# 26_PP0_SSMII.net
KiCad netlist of a schematic drawn in Altium Designer
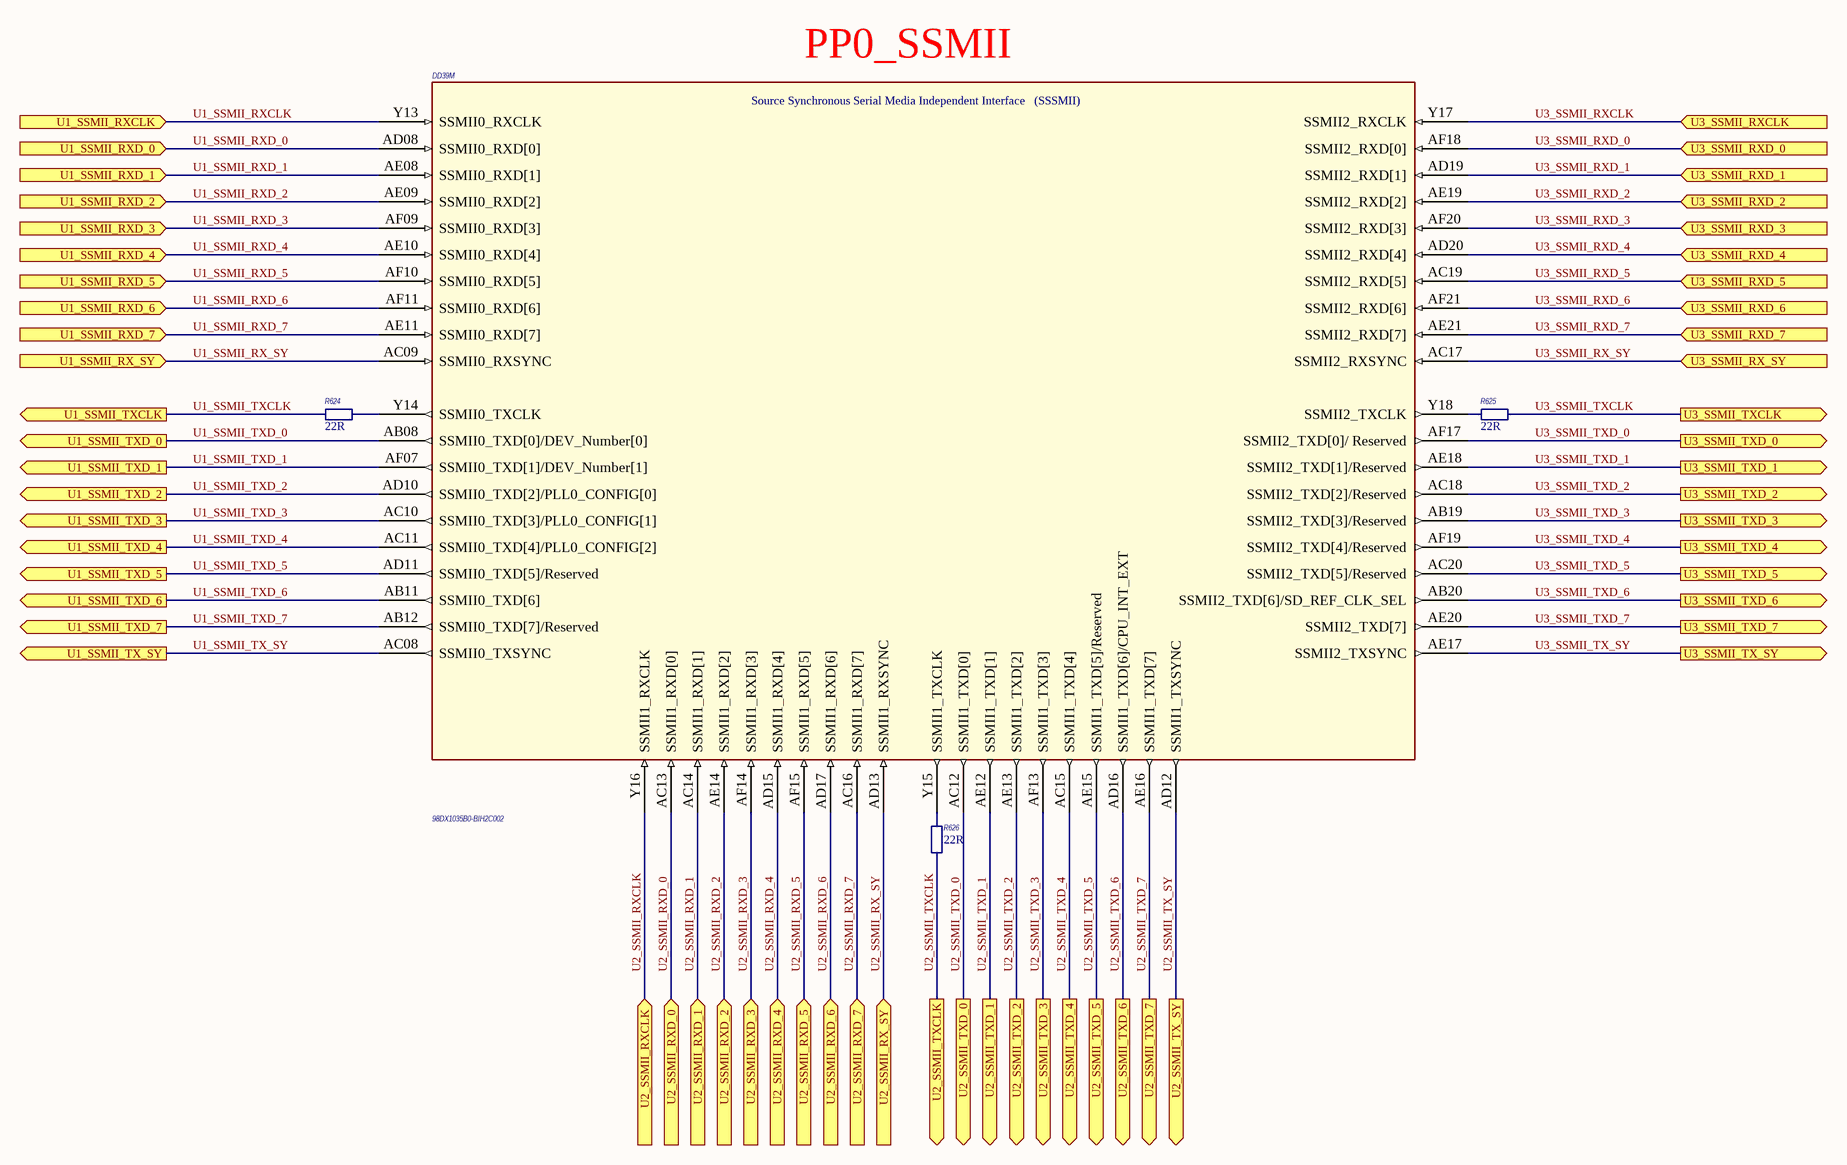
[diagram p0: 26_PP0_SSMII.SchDoc]

(export (version "E")
  (design (tool "Eeschema 10.0.6"))
  (components
    (comp (ref "DD39")
      (value "98DX1035B0-BIH2C002")
      (footprint "HSBGA617_27X27_1MM")
      (description "IC 24-PORT FE  4-PORT 2.5GE L2 ENTRY-LEVEL, CPU")
      (fields
        (field (name "CUSTOMER PART NUMBER") "Микросхема, 98DX1035B0-BIH2C002, IC 24-PORT FE 4-PORT 2.5GE L2 ENTRY-LEVEL, HSBGA617SBGA617")
        (field (name "MANUFACTURER") "Marvell Technology Group")
      )
      (libsource (lib "DIGITAL and ANALIG ICs") (part "98DX1035A1-BIH2C002"))
    )
    (comp (ref "R624")
      (value "ERJ-2RKF22R0X")
      (footprint "R0402_IPC High Density")
      (description "R0402, 22R 1%")
      (fields
        (field (name "MANUFACTURER") "Panasonic")
        (field (name "RESISTANCE") "22R")
        (field (name "CUSTOMER PART NUMBER") "Резистор, 22R, 0402, 1%")
      )
      (libsource (lib "RESISTOR") (part "ERJ-2RKF22R0X"))
    )
    (comp (ref "R625")
      (value "ERJ-2RKF22R0X")
      (footprint "R0402_IPC High Density")
      (description "R0402, 22R 1%")
      (fields
        (field (name "MANUFACTURER") "Panasonic")
        (field (name "RESISTANCE") "22R")
        (field (name "CUSTOMER PART NUMBER") "Резистор, 22R, 0402, 1%")
      )
      (libsource (lib "RESISTOR") (part "ERJ-2RKF22R0X"))
    )
    (comp (ref "R626")
      (value "ERJ-2RKF22R0X")
      (footprint "R0402_IPC High Density")
      (description "R0402, 22R 1%")
      (fields
        (field (name "MANUFACTURER") "Panasonic")
        (field (name "RESISTANCE") "22R")
        (field (name "CUSTOMER PART NUMBER") "Резистор, 22R, 0402, 1%")
      )
      (libsource (lib "RESISTOR") (part "ERJ-2RKF22R0X"))
    )
  )
  (nets
    (net (code "1") (name "/U1_SSMII_RXCLK") (class "Default")
      (node (ref "DD39") (pin "Y13") (pinfunction "SSMII0_RXCLK_Y13") (pintype "input"))
    )
    (net (code "2") (name "/U1_SSMII_RXD_0") (class "Default")
      (node (ref "DD39") (pin "AD08") (pinfunction "SSMII0_RXD[0]_AD08") (pintype "input"))
    )
    (net (code "3") (name "/U1_SSMII_RXD_1") (class "Default")
      (node (ref "DD39") (pin "AE08") (pinfunction "SSMII0_RXD[1]_AE08") (pintype "input"))
    )
    (net (code "4") (name "/U1_SSMII_RXD_2") (class "Default")
      (node (ref "DD39") (pin "AE09") (pinfunction "SSMII0_RXD[2]_AE09") (pintype "input"))
    )
    (net (code "5") (name "/U1_SSMII_RXD_3") (class "Default")
      (node (ref "DD39") (pin "AF09") (pinfunction "SSMII0_RXD[3]_AF09") (pintype "input"))
    )
    (net (code "6") (name "/U1_SSMII_RXD_4") (class "Default")
      (node (ref "DD39") (pin "AE10") (pinfunction "SSMII0_RXD[4]_AE10") (pintype "input"))
    )
    (net (code "7") (name "/U1_SSMII_RXD_5") (class "Default")
      (node (ref "DD39") (pin "AF10") (pinfunction "SSMII0_RXD[5]_AF10") (pintype "input"))
    )
    (net (code "8") (name "/U1_SSMII_RXD_6") (class "Default")
      (node (ref "DD39") (pin "AF11") (pinfunction "SSMII0_RXD[6]_AF11") (pintype "input"))
    )
    (net (code "9") (name "/U1_SSMII_RXD_7") (class "Default")
      (node (ref "DD39") (pin "AE11") (pinfunction "SSMII0_RXD[7]_AE11") (pintype "input"))
    )
    (net (code "10") (name "/U1_SSMII_RX_SY") (class "Default")
      (node (ref "DD39") (pin "AC09") (pinfunction "SSMII0_RXSYNC_AC09") (pintype "input"))
    )
    (net (code "11") (name "/U1_SSMII_TXCLK") (class "Default")
      (node (ref "R624") (pin "2") (pintype "passive"))
    )
    (net (code "12") (name "/U1_SSMII_TXD_0") (class "Default")
      (node (ref "DD39") (pin "AB08") (pinfunction "SSMII0_TXD[0]/DEV_Number[0]_AB08") (pintype "output"))
    )
    (net (code "13") (name "/U1_SSMII_TXD_1") (class "Default")
      (node (ref "DD39") (pin "AF07") (pinfunction "SSMII0_TXD[1]/DEV_Number[1]_AF07") (pintype "output"))
    )
    (net (code "14") (name "/U1_SSMII_TXD_2") (class "Default")
      (node (ref "DD39") (pin "AD10") (pinfunction "SSMII0_TXD[2]/PLL0_CONFIG[0]_AD10") (pintype "output"))
    )
    (net (code "15") (name "/U1_SSMII_TXD_3") (class "Default")
      (node (ref "DD39") (pin "AC10") (pinfunction "SSMII0_TXD[3]/PLL0_CONFIG[1]_AC10") (pintype "output"))
    )
    (net (code "16") (name "/U1_SSMII_TXD_4") (class "Default")
      (node (ref "DD39") (pin "AC11") (pinfunction "SSMII0_TXD[4]/PLL0_CONFIG[2]_AC11") (pintype "output"))
    )
    (net (code "17") (name "/U1_SSMII_TXD_5") (class "Default")
      (node (ref "DD39") (pin "AD11") (pinfunction "SSMII0_TXD[5]/Reserved_AD11") (pintype "output"))
    )
    (net (code "18") (name "/U1_SSMII_TXD_6") (class "Default")
      (node (ref "DD39") (pin "AB11") (pinfunction "SSMII0_TXD[6]_AB11") (pintype "output"))
    )
    (net (code "19") (name "/U1_SSMII_TXD_7") (class "Default")
      (node (ref "DD39") (pin "AB12") (pinfunction "SSMII0_TXD[7]/Reserved_AB12") (pintype "output"))
    )
    (net (code "20") (name "/U1_SSMII_TX_SY") (class "Default")
      (node (ref "DD39") (pin "AC08") (pinfunction "SSMII0_TXSYNC_AC08") (pintype "output"))
    )
    (net (code "21") (name "/U2_SSMII_RXCLK") (class "Default")
      (node (ref "DD39") (pin "Y16") (pinfunction "SSMII1_RXCLK_Y16") (pintype "input"))
    )
    (net (code "22") (name "/U2_SSMII_RXD_0") (class "Default")
      (node (ref "DD39") (pin "AC13") (pinfunction "SSMII1_RXD[0]_AC13") (pintype "input"))
    )
    (net (code "23") (name "/U2_SSMII_RXD_1") (class "Default")
      (node (ref "DD39") (pin "AC14") (pinfunction "SSMII1_RXD[1]_AC14") (pintype "input"))
    )
    (net (code "24") (name "/U2_SSMII_RXD_2") (class "Default")
      (node (ref "DD39") (pin "AE14") (pinfunction "SSMII1_RXD[2]_AE14") (pintype "input"))
    )
    (net (code "25") (name "/U2_SSMII_RXD_3") (class "Default")
      (node (ref "DD39") (pin "AF14") (pinfunction "SSMII1_RXD[3]_AF14") (pintype "input"))
    )
    (net (code "26") (name "/U2_SSMII_RXD_4") (class "Default")
      (node (ref "DD39") (pin "AD15") (pinfunction "SSMII1_RXD[4]_AD15") (pintype "input"))
    )
    (net (code "27") (name "/U2_SSMII_RXD_5") (class "Default")
      (node (ref "DD39") (pin "AF15") (pinfunction "SSMII1_RXD[5]_AF15") (pintype "input"))
    )
    (net (code "28") (name "/U2_SSMII_RXD_6") (class "Default")
      (node (ref "DD39") (pin "AD17") (pinfunction "SSMII1_RXD[6]_AD17") (pintype "input"))
    )
    (net (code "29") (name "/U2_SSMII_RXD_7") (class "Default")
      (node (ref "DD39") (pin "AC16") (pinfunction "SSMII1_RXD[7]_AC16") (pintype "input"))
    )
    (net (code "30") (name "/U2_SSMII_RX_SY") (class "Default")
      (node (ref "DD39") (pin "AD13") (pinfunction "SSMII1_RXSYNC_AD13") (pintype "input"))
    )
    (net (code "31") (name "/U2_SSMII_TXCLK") (class "Default")
      (node (ref "R626") (pin "2") (pintype "passive"))
    )
    (net (code "32") (name "/U2_SSMII_TXD_0") (class "Default")
      (node (ref "DD39") (pin "AC12") (pinfunction "SSMII1_TXD[0]_AC12") (pintype "output"))
    )
    (net (code "33") (name "/U2_SSMII_TXD_1") (class "Default")
      (node (ref "DD39") (pin "AE12") (pinfunction "SSMII1_TXD[1]_AE12") (pintype "output"))
    )
    (net (code "34") (name "/U2_SSMII_TXD_2") (class "Default")
      (node (ref "DD39") (pin "AE13") (pinfunction "SSMII1_TXD[2]_AE13") (pintype "output"))
    )
    (net (code "35") (name "/U2_SSMII_TXD_3") (class "Default")
      (node (ref "DD39") (pin "AF13") (pinfunction "SSMII1_TXD[3]_AF13") (pintype "output"))
    )
    (net (code "36") (name "/U2_SSMII_TXD_4") (class "Default")
      (node (ref "DD39") (pin "AC15") (pinfunction "SSMII1_TXD[4]_AC15") (pintype "output"))
    )
    (net (code "37") (name "/U2_SSMII_TXD_5") (class "Default")
      (node (ref "DD39") (pin "AE15") (pinfunction "SSMII1_TXD[5]/Reserved_AE15") (pintype "output"))
    )
    (net (code "38") (name "/U2_SSMII_TXD_6") (class "Default")
      (node (ref "DD39") (pin "AD16") (pinfunction "SSMII1_TXD[6]/CPU_INT_EXT_AD16") (pintype "output"))
    )
    (net (code "39") (name "/U2_SSMII_TXD_7") (class "Default")
      (node (ref "DD39") (pin "AE16") (pinfunction "SSMII1_TXD[7]_AE16") (pintype "output"))
    )
    (net (code "40") (name "/U2_SSMII_TX_SY") (class "Default")
      (node (ref "DD39") (pin "AD12") (pinfunction "SSMII1_TXSYNC_AD12") (pintype "output"))
    )
    (net (code "41") (name "/U3_SSMII_RXCLK") (class "Default")
      (node (ref "DD39") (pin "Y17") (pinfunction "SSMII2_RXCLK_Y17") (pintype "input"))
    )
    (net (code "42") (name "/U3_SSMII_RXD_0") (class "Default")
      (node (ref "DD39") (pin "AF18") (pinfunction "SSMII2_RXD[0]_AF18") (pintype "input"))
    )
    (net (code "43") (name "/U3_SSMII_RXD_1") (class "Default")
      (node (ref "DD39") (pin "AD19") (pinfunction "SSMII2_RXD[1]_AD19") (pintype "input"))
    )
    (net (code "44") (name "/U3_SSMII_RXD_2") (class "Default")
      (node (ref "DD39") (pin "AE19") (pinfunction "SSMII2_RXD[2]_AE19") (pintype "input"))
    )
    (net (code "45") (name "/U3_SSMII_RXD_3") (class "Default")
      (node (ref "DD39") (pin "AF20") (pinfunction "SSMII2_RXD[3]_AF20") (pintype "input"))
    )
    (net (code "46") (name "/U3_SSMII_RXD_4") (class "Default")
      (node (ref "DD39") (pin "AD20") (pinfunction "SSMII2_RXD[4]_AD20") (pintype "input"))
    )
    (net (code "47") (name "/U3_SSMII_RXD_5") (class "Default")
      (node (ref "DD39") (pin "AC19") (pinfunction "SSMII2_RXD[5]_AC19") (pintype "input"))
    )
    (net (code "48") (name "/U3_SSMII_RXD_6") (class "Default")
      (node (ref "DD39") (pin "AF21") (pinfunction "SSMII2_RXD[6]_AF21") (pintype "input"))
    )
    (net (code "49") (name "/U3_SSMII_RXD_7") (class "Default")
      (node (ref "DD39") (pin "AE21") (pinfunction "SSMII2_RXD[7]_AE21") (pintype "input"))
    )
    (net (code "50") (name "/U3_SSMII_RX_SY") (class "Default")
      (node (ref "DD39") (pin "AC17") (pinfunction "SSMII2_RXSYNC_AC17") (pintype "input"))
    )
    (net (code "51") (name "/U3_SSMII_TXCLK") (class "Default")
      (node (ref "R625") (pin "1") (pintype "passive"))
    )
    (net (code "52") (name "/U3_SSMII_TXD_0") (class "Default")
      (node (ref "DD39") (pin "AF17") (pinfunction "SSMII2_TXD[0]/_Reserved_AF17") (pintype "output"))
    )
    (net (code "53") (name "/U3_SSMII_TXD_1") (class "Default")
      (node (ref "DD39") (pin "AE18") (pinfunction "SSMII2_TXD[1]/Reserved_AE18") (pintype "output"))
    )
    (net (code "54") (name "/U3_SSMII_TXD_2") (class "Default")
      (node (ref "DD39") (pin "AC18") (pinfunction "SSMII2_TXD[2]/Reserved_AC18") (pintype "output"))
    )
    (net (code "55") (name "/U3_SSMII_TXD_3") (class "Default")
      (node (ref "DD39") (pin "AB19") (pinfunction "SSMII2_TXD[3]/Reserved_AB19") (pintype "output"))
    )
    (net (code "56") (name "/U3_SSMII_TXD_4") (class "Default")
      (node (ref "DD39") (pin "AF19") (pinfunction "SSMII2_TXD[4]/Reserved_AF19") (pintype "output"))
    )
    (net (code "57") (name "/U3_SSMII_TXD_5") (class "Default")
      (node (ref "DD39") (pin "AC20") (pinfunction "SSMII2_TXD[5]/Reserved_AC20") (pintype "output"))
    )
    (net (code "58") (name "/U3_SSMII_TXD_6") (class "Default")
      (node (ref "DD39") (pin "AB20") (pinfunction "SSMII2_TXD[6]/SD_REF_CLK_SEL_AB20") (pintype "output"))
    )
    (net (code "59") (name "/U3_SSMII_TXD_7") (class "Default")
      (node (ref "DD39") (pin "AE20") (pinfunction "SSMII2_TXD[7]_AE20") (pintype "output"))
    )
    (net (code "60") (name "/U3_SSMII_TX_SY") (class "Default")
      (node (ref "DD39") (pin "AE17") (pinfunction "SSMII2_TXSYNC_AE17") (pintype "output"))
    )
    (net (code "61") (name "Net-(DD39M-SSMII0_TXCLK)") (class "Default")
      (node (ref "DD39") (pin "Y14") (pinfunction "SSMII0_TXCLK_Y14") (pintype "output"))
      (node (ref "R624") (pin "1") (pintype "passive"))
    )
    (net (code "62") (name "Net-(DD39M-SSMII1_TXCLK)") (class "Default")
      (node (ref "DD39") (pin "Y15") (pinfunction "SSMII1_TXCLK_Y15") (pintype "output"))
      (node (ref "R626") (pin "1") (pintype "passive"))
    )
    (net (code "63") (name "Net-(DD39M-SSMII2_TXCLK)") (class "Default")
      (node (ref "DD39") (pin "Y18") (pinfunction "SSMII2_TXCLK_Y18") (pintype "output"))
      (node (ref "R625") (pin "2") (pintype "passive"))
    )
  )
)
